# SCH_Arduino_Nano.net
KiCad netlist of a schematic drawn in Altium Designer
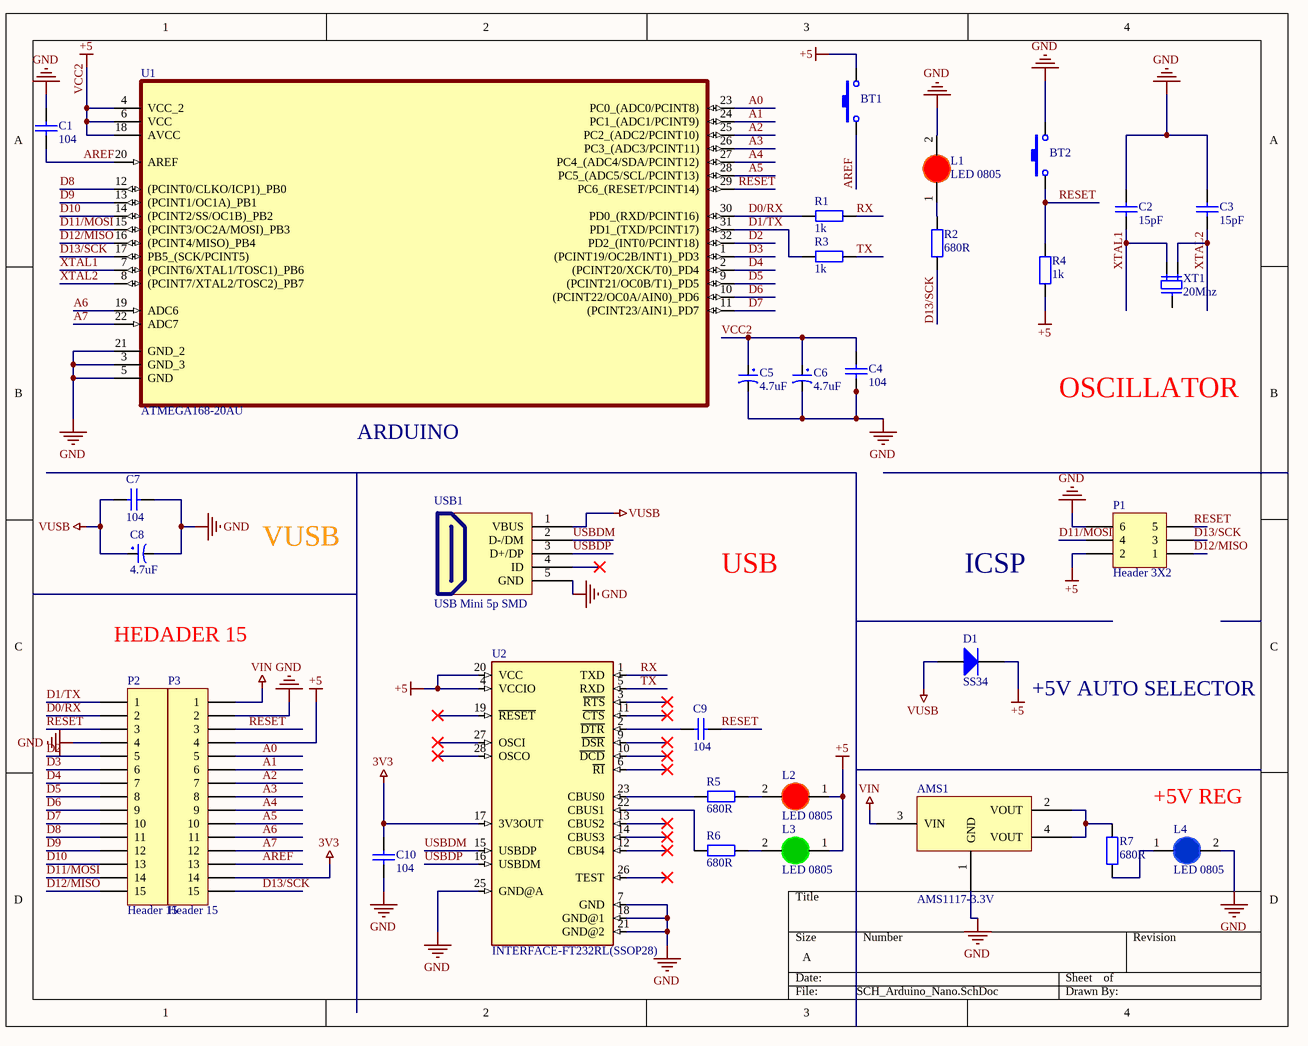
[diagram p0: SCH_Arduino_Nano.SchDoc]

(export (version "E")
  (design (tool "Eeschema 10.0.6"))
  (components
    (comp (ref "AMS1")
      (value "AMS1117-3.3V")
      (footprint "SOT223")
      (description "Dán")
      (libsource (lib "Altium_Lib_by_KhueNguyenCreator") (part "AMS1117 SMD"))
    )
    (comp (ref "BT1")
      (value "Nut Nhan 2 Chan SMD 3x6x2.5")
      (footprint "Nut Nhan 2 Chan SMD 3x6x2.5")
      (libsource (lib "Altium_Lib_by_KhueNguyenCreator") (part "Nut Nhan 2 Chan SMD 3x6x2.5"))
    )
    (comp (ref "BT2")
      (value "Nut Nhan 2 Chan SMD 3x6x2.5")
      (footprint "Nut Nhan 2 Chan SMD 3x6x2.5")
      (libsource (lib "Altium_Lib_by_KhueNguyenCreator") (part "Nut Nhan 2 Chan SMD 3x6x2.5"))
    )
    (comp (ref "C1")
      (value "104")
      (footprint "tu 0603")
      (description "Dán")
      (libsource (lib "Altium_Lib_by_KhueNguyenCreator") (part "Tu 0603 104 50V 10%"))
    )
    (comp (ref "C2")
      (value "15pF")
      (footprint "tu 0805")
      (description "Dán")
      (libsource (lib "Altium_Lib_by_KhueNguyenCreator") (part "Tu 0805 15pF 50V 10%"))
    )
    (comp (ref "C3")
      (value "15pF")
      (footprint "tu 0805")
      (description "Dán")
      (libsource (lib "Altium_Lib_by_KhueNguyenCreator") (part "Tu 0805 15pF 50V 10%"))
    )
    (comp (ref "C4")
      (value "104")
      (footprint "tu 0603")
      (description "Dán")
      (libsource (lib "Altium_Lib_by_KhueNguyenCreator") (part "Tu 0603 104 50V 10%"))
    )
    (comp (ref "C5")
      (value "4.7uF")
      (footprint "tu tantalum smd6032")
      (description "Dán")
      (libsource (lib "Altium_Lib_by_KhueNguyenCreator") (part "Tu tantalum 4.7uF 35V SMD6032"))
    )
    (comp (ref "C6")
      (value "4.7uF")
      (footprint "tu tantalum smd6032")
      (description "Dán")
      (libsource (lib "Altium_Lib_by_KhueNguyenCreator") (part "Tu tantalum 4.7uF 35V SMD6032"))
    )
    (comp (ref "C7")
      (value "104")
      (footprint "tu 0603")
      (description "Dán")
      (libsource (lib "Altium_Lib_by_KhueNguyenCreator") (part "Tu 0603 104 50V 10%"))
    )
    (comp (ref "C8")
      (value "4.7uF")
      (footprint "tu tantalum smd6032")
      (description "Dán")
      (libsource (lib "") (part "Tu tantalum 4.7uF 35V SMD6032_1"))
    )
    (comp (ref "C9")
      (value "104")
      (footprint "tu 0603")
      (description "Dán")
      (libsource (lib "Altium_Lib_by_KhueNguyenCreator") (part "Tu 0603 104 50V 10%"))
    )
    (comp (ref "C10")
      (value "104")
      (footprint "tu 0603")
      (description "Dán")
      (libsource (lib "Altium_Lib_by_KhueNguyenCreator") (part "Tu 0603 104 50V 10%"))
    )
    (comp (ref "D1")
      (value "SS34")
      (footprint "DIODE SMA")
      (description "Dán")
      (libsource (lib "Altium_Lib_by_KhueNguyenCreator") (part "Diode SS34 ( 1N5822 )"))
    )
    (comp (ref "L1")
      (value "LED 0805")
      (footprint "LED-0805-Red")
      (description "Dán")
      (libsource (lib "Altium_Lib_by_KhueNguyenCreator") (part "LED 0805 Do"))
    )
    (comp (ref "L2")
      (value "LED 0805")
      (footprint "LED-0805-Red")
      (description "Dán")
      (libsource (lib "Altium_Lib_by_KhueNguyenCreator") (part "LED 0805 Do"))
    )
    (comp (ref "L3")
      (value "LED 0805")
      (footprint "LED-0805-Green")
      (description "Dán")
      (libsource (lib "Altium_Lib_by_KhueNguyenCreator") (part "LED 0805 Xanh La"))
    )
    (comp (ref "L4")
      (value "LED 0805")
      (footprint "LED-0805-Blue")
      (description "Dán")
      (libsource (lib "Altium_Lib_by_KhueNguyenCreator") (part "LED 0805 Xanh Duong"))
    )
    (comp (ref "P1")
      (value "Header 3X2")
      (footprint "HDR2X3")
      (description "Header, 3-Pin, Dual row")
      (fields (field (name "PUBLISHER") "Altium Limited"))
      (libsource (lib "Miscellaneous Connectors") (part "Header 3X2"))
    )
    (comp (ref "P2")
      (value "Header 15")
      (footprint "HDR1X15")
      (description "Header, 15-Pin")
      (fields (field (name "PUBLISHER") "Altium Limited"))
      (libsource (lib "Miscellaneous Connectors") (part "Header 15"))
    )
    (comp (ref "P3")
      (value "Header 15")
      (footprint "HDR1X15")
      (description "Header, 15-Pin")
      (fields (field (name "PUBLISHER") "Altium Limited"))
      (libsource (lib "") (part "Header 15_1"))
    )
    (comp (ref "R1")
      (value "1k")
      (footprint "tro smd 0603")
      (description "Dán")
      (libsource (lib "Altium_Lib_by_KhueNguyenCreator") (part "Tro 0603 5% 1k"))
    )
    (comp (ref "R2")
      (value "680R")
      (footprint "Tro SMD 0805")
      (description "Dán")
      (libsource (lib "Altium_Lib_by_KhueNguyenCreator") (part "Tro 0805 5% 680R"))
    )
    (comp (ref "R3")
      (value "1k")
      (footprint "tro smd 0603")
      (description "Dán")
      (libsource (lib "Altium_Lib_by_KhueNguyenCreator") (part "Tro 0603 5% 1k"))
    )
    (comp (ref "R4")
      (value "1k")
      (footprint "tro smd 0805")
      (description "Dán")
      (libsource (lib "Altium_Lib_by_KhueNguyenCreator") (part "Tro 0805 5% 1k"))
    )
    (comp (ref "R5")
      (value "680R")
      (footprint "tro smd 0603")
      (description "Dán")
      (libsource (lib "Altium_Lib_by_KhueNguyenCreator") (part "Tro 0603 1% 680R"))
    )
    (comp (ref "R6")
      (value "680R")
      (footprint "tro smd 0603")
      (description "Dán")
      (libsource (lib "Altium_Lib_by_KhueNguyenCreator") (part "Tro 0603 1% 680R"))
    )
    (comp (ref "R7")
      (value "680R")
      (footprint "tro smd 0603")
      (description "Dán")
      (libsource (lib "Altium_Lib_by_KhueNguyenCreator") (part "Tro 0603 1% 680R"))
    )
    (comp (ref "U1")
      (value "ATMEGA168-20AU")
      (footprint "QFP80P900X900X120-32N")
      (description "AVR AVRÂ® ATmega Microcontroller IC 8-Bit 20MHz 16KB _8K x 16_ FLASH 32-TQFP _7x7_")
      (fields (field (name "MF") "Microchip"))
      (libsource (lib "ATMEGA168-20AU") (part "ATMEGA168-20AU"))
    )
    (comp (ref "U2")
      (value "INTERFACE-FT232RL(SSOP28)")
      (footprint "SSOP28-0.65-10.2X5.2MM")
      (description "USB Bridge, USB to UART USB 2.0 UART Interface 28-SSOP")
      (fields (field (name "MP") "FT232RL") (field (name "MF") "FTDI, Future"))
      (libsource (lib "INTERFACE-FT232RL_SSOP28_") (part "INTERFACE-FT232RL(SSOP28)"))
    )
    (comp (ref "USB1")
      (value "USB Mini 5p SMD")
      (footprint "USB Mini 5p SMD")
      (description "USB Type B")
      (libsource (lib "Altium_Lib_by_KhueNguyenCreator") (part "USB Mini 5p SMD"))
    )
    (comp (ref "XT1")
      (value "20Mhz")
      (footprint "Thach Anh 3 Chan SMD")
      (description "Crystal For all Crystal 2pin.")
      (libsource (lib "Altium_Lib_by_KhueNguyenCreator") (part "Thach anh 3 Chan SMD"))
    )
  )
  (nets
    (net (code "1") (name "+5") (class "Default")
      (node (ref "BT1") (pin "2") (pinfunction "2_2") (pintype "passive"))
      (node (ref "C4") (pin "1") (pinfunction "1_1") (pintype "passive"))
      (node (ref "C5") (pin "1") (pinfunction "1_1") (pintype "passive"))
      (node (ref "C6") (pin "1") (pinfunction "1_1") (pintype "passive"))
      (node (ref "D1") (pin "2") (pinfunction "K_2") (pintype "passive"))
      (node (ref "L2") (pin "1") (pinfunction "A_1") (pintype "passive"))
      (node (ref "L3") (pin "1") (pinfunction "A_1") (pintype "passive"))
      (node (ref "P1") (pin "2") (pinfunction "2_2") (pintype "passive"))
      (node (ref "P3") (pin "4") (pinfunction "4_4") (pintype "passive"))
      (node (ref "R4") (pin "1") (pinfunction "1_1") (pintype "passive"))
      (node (ref "U1") (pin "18") (pinfunction "AVCC_18") (pintype "power_in"))
      (node (ref "U1") (pin "4") (pinfunction "VCC_2_4") (pintype "power_in"))
      (node (ref "U1") (pin "6") (pinfunction "VCC_6") (pintype "power_in"))
      (node (ref "U2") (pin "20") (pinfunction "VCC_20") (pintype "input"))
      (node (ref "U2") (pin "4") (pinfunction "VCCIO_4") (pintype "input"))
    )
    (net (code "2") (name "/A0") (class "Default")
      (node (ref "P3") (pin "5") (pinfunction "5_5") (pintype "passive"))
      (node (ref "U1") (pin "23") (pinfunction "PC0_(ADC0/PCINT8)_23") (pintype "bidirectional"))
    )
    (net (code "3") (name "/A1") (class "Default")
      (node (ref "P3") (pin "6") (pinfunction "6_6") (pintype "passive"))
      (node (ref "U1") (pin "24") (pinfunction "PC1_(ADC1/PCINT9)_24") (pintype "bidirectional"))
    )
    (net (code "4") (name "/A2") (class "Default")
      (node (ref "P3") (pin "7") (pinfunction "7_7") (pintype "passive"))
      (node (ref "U1") (pin "25") (pinfunction "PC2_(ADC2/PCINT10)_25") (pintype "bidirectional"))
    )
    (net (code "5") (name "/A3") (class "Default")
      (node (ref "P3") (pin "8") (pinfunction "8_8") (pintype "passive"))
      (node (ref "U1") (pin "26") (pinfunction "PC3_(ADC3/PCINT11)_26") (pintype "bidirectional"))
    )
    (net (code "6") (name "/A4") (class "Default")
      (node (ref "P3") (pin "9") (pinfunction "9_9") (pintype "passive"))
      (node (ref "U1") (pin "27") (pinfunction "PC4_(ADC4/SDA/PCINT12)_27") (pintype "bidirectional"))
    )
    (net (code "7") (name "/A5") (class "Default")
      (node (ref "P3") (pin "10") (pinfunction "10_10") (pintype "passive"))
      (node (ref "U1") (pin "28") (pinfunction "PC5_(ADC5/SCL/PCINT13)_28") (pintype "bidirectional"))
    )
    (net (code "8") (name "/A6") (class "Default")
      (node (ref "P3") (pin "11") (pinfunction "11_11") (pintype "passive"))
      (node (ref "U1") (pin "19") (pinfunction "ADC6_19") (pintype "input"))
    )
    (net (code "9") (name "/A7") (class "Default")
      (node (ref "P3") (pin "12") (pinfunction "12_12") (pintype "passive"))
      (node (ref "U1") (pin "22") (pinfunction "ADC7_22") (pintype "input"))
    )
    (net (code "10") (name "/AREF") (class "Default")
      (node (ref "BT1") (pin "1") (pinfunction "1_1") (pintype "passive"))
      (node (ref "C1") (pin "1") (pinfunction "1_1") (pintype "passive"))
      (node (ref "P3") (pin "13") (pinfunction "13_13") (pintype "passive"))
      (node (ref "U1") (pin "20") (pinfunction "AREF_20") (pintype "input"))
    )
    (net (code "11") (name "/D0{slash}RX") (class "Default")
      (node (ref "P2") (pin "2") (pinfunction "2_2") (pintype "passive"))
      (node (ref "R1") (pin "1") (pinfunction "1_1") (pintype "passive"))
      (node (ref "U1") (pin "30") (pinfunction "PD0_(RXD/PCINT16)_30") (pintype "bidirectional"))
    )
    (net (code "12") (name "/D1{slash}TX") (class "Default")
      (node (ref "P2") (pin "1") (pinfunction "1_1") (pintype "passive"))
      (node (ref "R3") (pin "1") (pinfunction "1_1") (pintype "passive"))
      (node (ref "U1") (pin "31") (pinfunction "PD1_(TXD/PCINT17)_31") (pintype "bidirectional"))
    )
    (net (code "13") (name "/D2") (class "Default")
      (node (ref "P2") (pin "5") (pinfunction "5_5") (pintype "passive"))
      (node (ref "U1") (pin "32") (pinfunction "PD2_(INT0/PCINT18)_32") (pintype "bidirectional"))
    )
    (net (code "14") (name "/D3") (class "Default")
      (node (ref "P2") (pin "6") (pinfunction "6_6") (pintype "passive"))
      (node (ref "U1") (pin "1") (pinfunction "(PCINT19/OC2B/INT1)_PD3_1") (pintype "bidirectional"))
    )
    (net (code "15") (name "/D4") (class "Default")
      (node (ref "P2") (pin "7") (pinfunction "7_7") (pintype "passive"))
      (node (ref "U1") (pin "2") (pinfunction "(PCINT20/XCK/T0)_PD4_2") (pintype "bidirectional"))
    )
    (net (code "16") (name "/D5") (class "Default")
      (node (ref "P2") (pin "8") (pinfunction "8_8") (pintype "passive"))
      (node (ref "U1") (pin "9") (pinfunction "(PCINT21/OC0B/T1)_PD5_9") (pintype "bidirectional"))
    )
    (net (code "17") (name "/D6") (class "Default")
      (node (ref "P2") (pin "9") (pinfunction "9_9") (pintype "passive"))
      (node (ref "U1") (pin "10") (pinfunction "(PCINT22/OC0A/AIN0)_PD6_10") (pintype "bidirectional"))
    )
    (net (code "18") (name "/D7") (class "Default")
      (node (ref "P2") (pin "10") (pinfunction "10_10") (pintype "passive"))
      (node (ref "U1") (pin "11") (pinfunction "(PCINT23/AIN1)_PD7_11") (pintype "bidirectional"))
    )
    (net (code "19") (name "/D8") (class "Default")
      (node (ref "P2") (pin "11") (pinfunction "11_11") (pintype "passive"))
      (node (ref "U1") (pin "12") (pinfunction "(PCINT0/CLKO/ICP1)_PB0_12") (pintype "bidirectional"))
    )
    (net (code "20") (name "/D9") (class "Default")
      (node (ref "P2") (pin "12") (pinfunction "12_12") (pintype "passive"))
      (node (ref "U1") (pin "13") (pinfunction "(PCINT1/OC1A)_PB1_13") (pintype "bidirectional"))
    )
    (net (code "21") (name "/D10") (class "Default")
      (node (ref "P2") (pin "13") (pinfunction "13_13") (pintype "passive"))
      (node (ref "U1") (pin "14") (pinfunction "(PCINT2/SS/OC1B)_PB2_14") (pintype "bidirectional"))
    )
    (net (code "22") (name "/D11{slash}MOSI") (class "Default")
      (node (ref "P1") (pin "4") (pinfunction "4_4") (pintype "passive"))
      (node (ref "P2") (pin "14") (pinfunction "14_14") (pintype "passive"))
      (node (ref "U1") (pin "15") (pinfunction "(PCINT3/OC2A/MOSI)_PB3_15") (pintype "bidirectional"))
    )
    (net (code "23") (name "/D12{slash}MISO") (class "Default")
      (node (ref "P1") (pin "1") (pinfunction "1_1") (pintype "passive"))
      (node (ref "P2") (pin "15") (pinfunction "15_15") (pintype "passive"))
      (node (ref "U1") (pin "16") (pinfunction "(PCINT4/MISO)_PB4_16") (pintype "bidirectional"))
    )
    (net (code "24") (name "/D13{slash}SCK") (class "Default")
      (node (ref "P1") (pin "3") (pinfunction "3_3") (pintype "passive"))
      (node (ref "P3") (pin "15") (pinfunction "15_15") (pintype "passive"))
      (node (ref "R2") (pin "2") (pinfunction "2_2") (pintype "passive"))
      (node (ref "U1") (pin "17") (pinfunction "PB5_(SCK/PCINT5)_17") (pintype "bidirectional"))
    )
    (net (code "25") (name "/RESET") (class "Default")
      (node (ref "BT2") (pin "2") (pinfunction "2_2") (pintype "passive"))
      (node (ref "C9") (pin "1") (pinfunction "1_1") (pintype "passive"))
      (node (ref "P1") (pin "5") (pinfunction "5_5") (pintype "passive"))
      (node (ref "P2") (pin "3") (pinfunction "3_3") (pintype "passive"))
      (node (ref "P3") (pin "3") (pinfunction "3_3") (pintype "passive"))
      (node (ref "R4") (pin "2") (pinfunction "2_2") (pintype "passive"))
      (node (ref "U1") (pin "29") (pinfunction "PC6_(RESET/PCINT14)_29") (pintype "bidirectional"))
    )
    (net (code "26") (name "/RX") (class "Default")
      (node (ref "R1") (pin "2") (pinfunction "2_2") (pintype "passive"))
      (node (ref "U2") (pin "1") (pinfunction "TXD_1") (pintype "input"))
    )
    (net (code "27") (name "/TX") (class "Default")
      (node (ref "R3") (pin "2") (pinfunction "2_2") (pintype "passive"))
      (node (ref "U2") (pin "5") (pinfunction "RXD_5") (pintype "input"))
    )
    (net (code "28") (name "/USBDM") (class "Default")
      (node (ref "U2") (pin "15") (pinfunction "USBDP_15") (pintype "input"))
      (node (ref "USB1") (pin "2") (pinfunction "D-/DM_2") (pintype "passive"))
    )
    (net (code "29") (name "/USBDP") (class "Default")
      (node (ref "U2") (pin "16") (pinfunction "USBDM_16") (pintype "input"))
      (node (ref "USB1") (pin "3") (pinfunction "D+/DP_3") (pintype "passive"))
    )
    (net (code "30") (name "/XTAL1") (class "Default")
      (node (ref "C2") (pin "1") (pinfunction "1_1") (pintype "passive"))
      (node (ref "U1") (pin "7") (pinfunction "(PCINT6/XTAL1/TOSC1)_PB6_7") (pintype "bidirectional"))
      (node (ref "XT1") (pin "1") (pinfunction "1_1") (pintype "passive"))
    )
    (net (code "31") (name "/XTAL2") (class "Default")
      (node (ref "C3") (pin "1") (pinfunction "1_1") (pintype "passive"))
      (node (ref "U1") (pin "8") (pinfunction "(PCINT7/XTAL2/TOSC2)_PB7_8") (pintype "bidirectional"))
      (node (ref "XT1") (pin "3") (pinfunction "3_3") (pintype "passive"))
    )
    (net (code "32") (name "3V3") (class "Default")
      (node (ref "C10") (pin "1") (pinfunction "1_1") (pintype "passive"))
      (node (ref "P3") (pin "14") (pinfunction "14_14") (pintype "passive"))
      (node (ref "U2") (pin "17") (pinfunction "3V3OUT_17") (pintype "input"))
    )
    (net (code "33") (name "GND") (class "Default")
      (node (ref "AMS1") (pin "1") (pinfunction "GND_1") (pintype "passive"))
      (node (ref "BT2") (pin "1") (pinfunction "1_1") (pintype "passive"))
      (node (ref "C1") (pin "2") (pinfunction "2_2") (pintype "passive"))
      (node (ref "C10") (pin "2") (pinfunction "2_2") (pintype "passive"))
      (node (ref "C2") (pin "2") (pinfunction "2_2") (pintype "passive"))
      (node (ref "C3") (pin "2") (pinfunction "2_2") (pintype "passive"))
      (node (ref "C4") (pin "2") (pinfunction "2_2") (pintype "passive"))
      (node (ref "C5") (pin "2") (pinfunction "2_2") (pintype "passive"))
      (node (ref "C6") (pin "2") (pinfunction "2_2") (pintype "passive"))
      (node (ref "C7") (pin "1") (pinfunction "1_1") (pintype "passive"))
      (node (ref "C8") (pin "2") (pinfunction "2_2") (pintype "passive"))
      (node (ref "L1") (pin "2") (pinfunction "K_2") (pintype "passive"))
      (node (ref "L4") (pin "2") (pinfunction "K_2") (pintype "passive"))
      (node (ref "P1") (pin "6") (pinfunction "6_6") (pintype "passive"))
      (node (ref "P2") (pin "4") (pinfunction "4_4") (pintype "passive"))
      (node (ref "P3") (pin "2") (pinfunction "2_2") (pintype "passive"))
      (node (ref "U1") (pin "21") (pinfunction "GND_2_21") (pintype "passive"))
      (node (ref "U1") (pin "3") (pinfunction "GND_3_3") (pintype "passive"))
      (node (ref "U1") (pin "5") (pinfunction "GND_5") (pintype "passive"))
      (node (ref "U2") (pin "18") (pinfunction "GND@1_18") (pintype "input"))
      (node (ref "U2") (pin "21") (pinfunction "GND@2_21") (pintype "input"))
      (node (ref "U2") (pin "25") (pinfunction "GND@A_25") (pintype "input"))
      (node (ref "U2") (pin "7") (pinfunction "GND_7") (pintype "input"))
      (node (ref "USB1") (pin "5") (pinfunction "GND_5") (pintype "passive"))
    )
    (net (code "34") (name "Net-(AMS1-VOUT-Pad2)") (class "Default")
      (node (ref "AMS1") (pin "2") (pinfunction "VOUT_2") (pintype "passive"))
      (node (ref "AMS1") (pin "4") (pinfunction "VOUT_4") (pintype "passive"))
      (node (ref "R7") (pin "2") (pinfunction "2_2") (pintype "passive"))
    )
    (net (code "35") (name "Net-(L1-A)") (class "Default")
      (node (ref "L1") (pin "1") (pinfunction "A_1") (pintype "passive"))
      (node (ref "R2") (pin "1") (pinfunction "1_1") (pintype "passive"))
    )
    (net (code "36") (name "Net-(L2-K)") (class "Default")
      (node (ref "L2") (pin "2") (pinfunction "K_2") (pintype "passive"))
      (node (ref "R5") (pin "2") (pinfunction "2_2") (pintype "passive"))
    )
    (net (code "37") (name "Net-(L3-K)") (class "Default")
      (node (ref "L3") (pin "2") (pinfunction "K_2") (pintype "passive"))
      (node (ref "R6") (pin "2") (pinfunction "2_2") (pintype "passive"))
    )
    (net (code "38") (name "Net-(L4-A)") (class "Default")
      (node (ref "L4") (pin "1") (pinfunction "A_1") (pintype "passive"))
      (node (ref "R7") (pin "1") (pinfunction "1_1") (pintype "passive"))
    )
    (net (code "39") (name "Net-(U2-CBUS0)") (class "Default")
      (node (ref "R5") (pin "1") (pinfunction "1_1") (pintype "passive"))
      (node (ref "U2") (pin "23") (pinfunction "CBUS0_23") (pintype "input"))
    )
    (net (code "40") (name "Net-(U2-CBUS1)") (class "Default")
      (node (ref "R6") (pin "1") (pinfunction "1_1") (pintype "passive"))
      (node (ref "U2") (pin "22") (pinfunction "CBUS1_22") (pintype "input"))
    )
    (net (code "41") (name "Net-(U2-~{DTR})") (class "Default")
      (node (ref "C9") (pin "2") (pinfunction "2_2") (pintype "passive"))
      (node (ref "U2") (pin "2") (pinfunction "~{DTR}_2") (pintype "input"))
    )
    (net (code "42") (name "VIN") (class "Default")
      (node (ref "AMS1") (pin "3") (pinfunction "VIN_3") (pintype "passive"))
      (node (ref "P3") (pin "1") (pinfunction "1_1") (pintype "passive"))
    )
    (net (code "43") (name "VUSB") (class "Default")
      (node (ref "C7") (pin "2") (pinfunction "2_2") (pintype "passive"))
      (node (ref "C8") (pin "1") (pinfunction "1_1") (pintype "passive"))
      (node (ref "D1") (pin "1") (pinfunction "A_1") (pintype "passive"))
      (node (ref "USB1") (pin "1") (pinfunction "VBUS_1") (pintype "passive"))
    )
    (net (code "44") (name "unconnected-(U2-CBUS2-Pad13)") (class "Default")
      (node (ref "U2") (pin "13") (pinfunction "CBUS2_13") (pintype "input+no_connect"))
    )
    (net (code "45") (name "unconnected-(U2-CBUS3-Pad14)") (class "Default")
      (node (ref "U2") (pin "14") (pinfunction "CBUS3_14") (pintype "input+no_connect"))
    )
    (net (code "46") (name "unconnected-(U2-CBUS4-Pad12)") (class "Default")
      (node (ref "U2") (pin "12") (pinfunction "CBUS4_12") (pintype "input+no_connect"))
    )
    (net (code "47") (name "unconnected-(U2-OSCI-Pad27)") (class "Default")
      (node (ref "U2") (pin "27") (pinfunction "OSCI_27") (pintype "input+no_connect"))
    )
    (net (code "48") (name "unconnected-(U2-OSCO-Pad28)") (class "Default")
      (node (ref "U2") (pin "28") (pinfunction "OSCO_28") (pintype "input+no_connect"))
    )
    (net (code "49") (name "unconnected-(U2-TEST-Pad26)") (class "Default")
      (node (ref "U2") (pin "26") (pinfunction "TEST_26") (pintype "input+no_connect"))
    )
    (net (code "50") (name "unconnected-(U2-~{CTS}-Pad11)") (class "Default")
      (node (ref "U2") (pin "11") (pinfunction "~{CTS}_11") (pintype "input+no_connect"))
    )
    (net (code "51") (name "unconnected-(U2-~{DCD}-Pad10)") (class "Default")
      (node (ref "U2") (pin "10") (pinfunction "~{DCD}_10") (pintype "input+no_connect"))
    )
    (net (code "52") (name "unconnected-(U2-~{DSR}-Pad9)") (class "Default")
      (node (ref "U2") (pin "9") (pinfunction "~{DSR}_9") (pintype "input+no_connect"))
    )
    (net (code "53") (name "unconnected-(U2-~{RESET}-Pad19)") (class "Default")
      (node (ref "U2") (pin "19") (pinfunction "~{RESET}_19") (pintype "input+no_connect"))
    )
    (net (code "54") (name "unconnected-(U2-~{RI}-Pad6)") (class "Default")
      (node (ref "U2") (pin "6") (pinfunction "~{RI}_6") (pintype "input+no_connect"))
    )
    (net (code "55") (name "unconnected-(U2-~{RTS}-Pad3)") (class "Default")
      (node (ref "U2") (pin "3") (pinfunction "~{RTS}_3") (pintype "input+no_connect"))
    )
    (net (code "56") (name "unconnected-(USB1-ID-Pad4)") (class "Default")
      (node (ref "USB1") (pin "4") (pinfunction "ID_4") (pintype "passive+no_connect"))
    )
    (net (code "57") (name "unconnected-(XT1-Pad2)") (class "Default")
      (node (ref "XT1") (pin "2") (pinfunction "2_2") (pintype "passive"))
    )
  )
)
